# MODUL_BRIDGE_V100.net
KiCad netlist of a schematic drawn in EAGLE
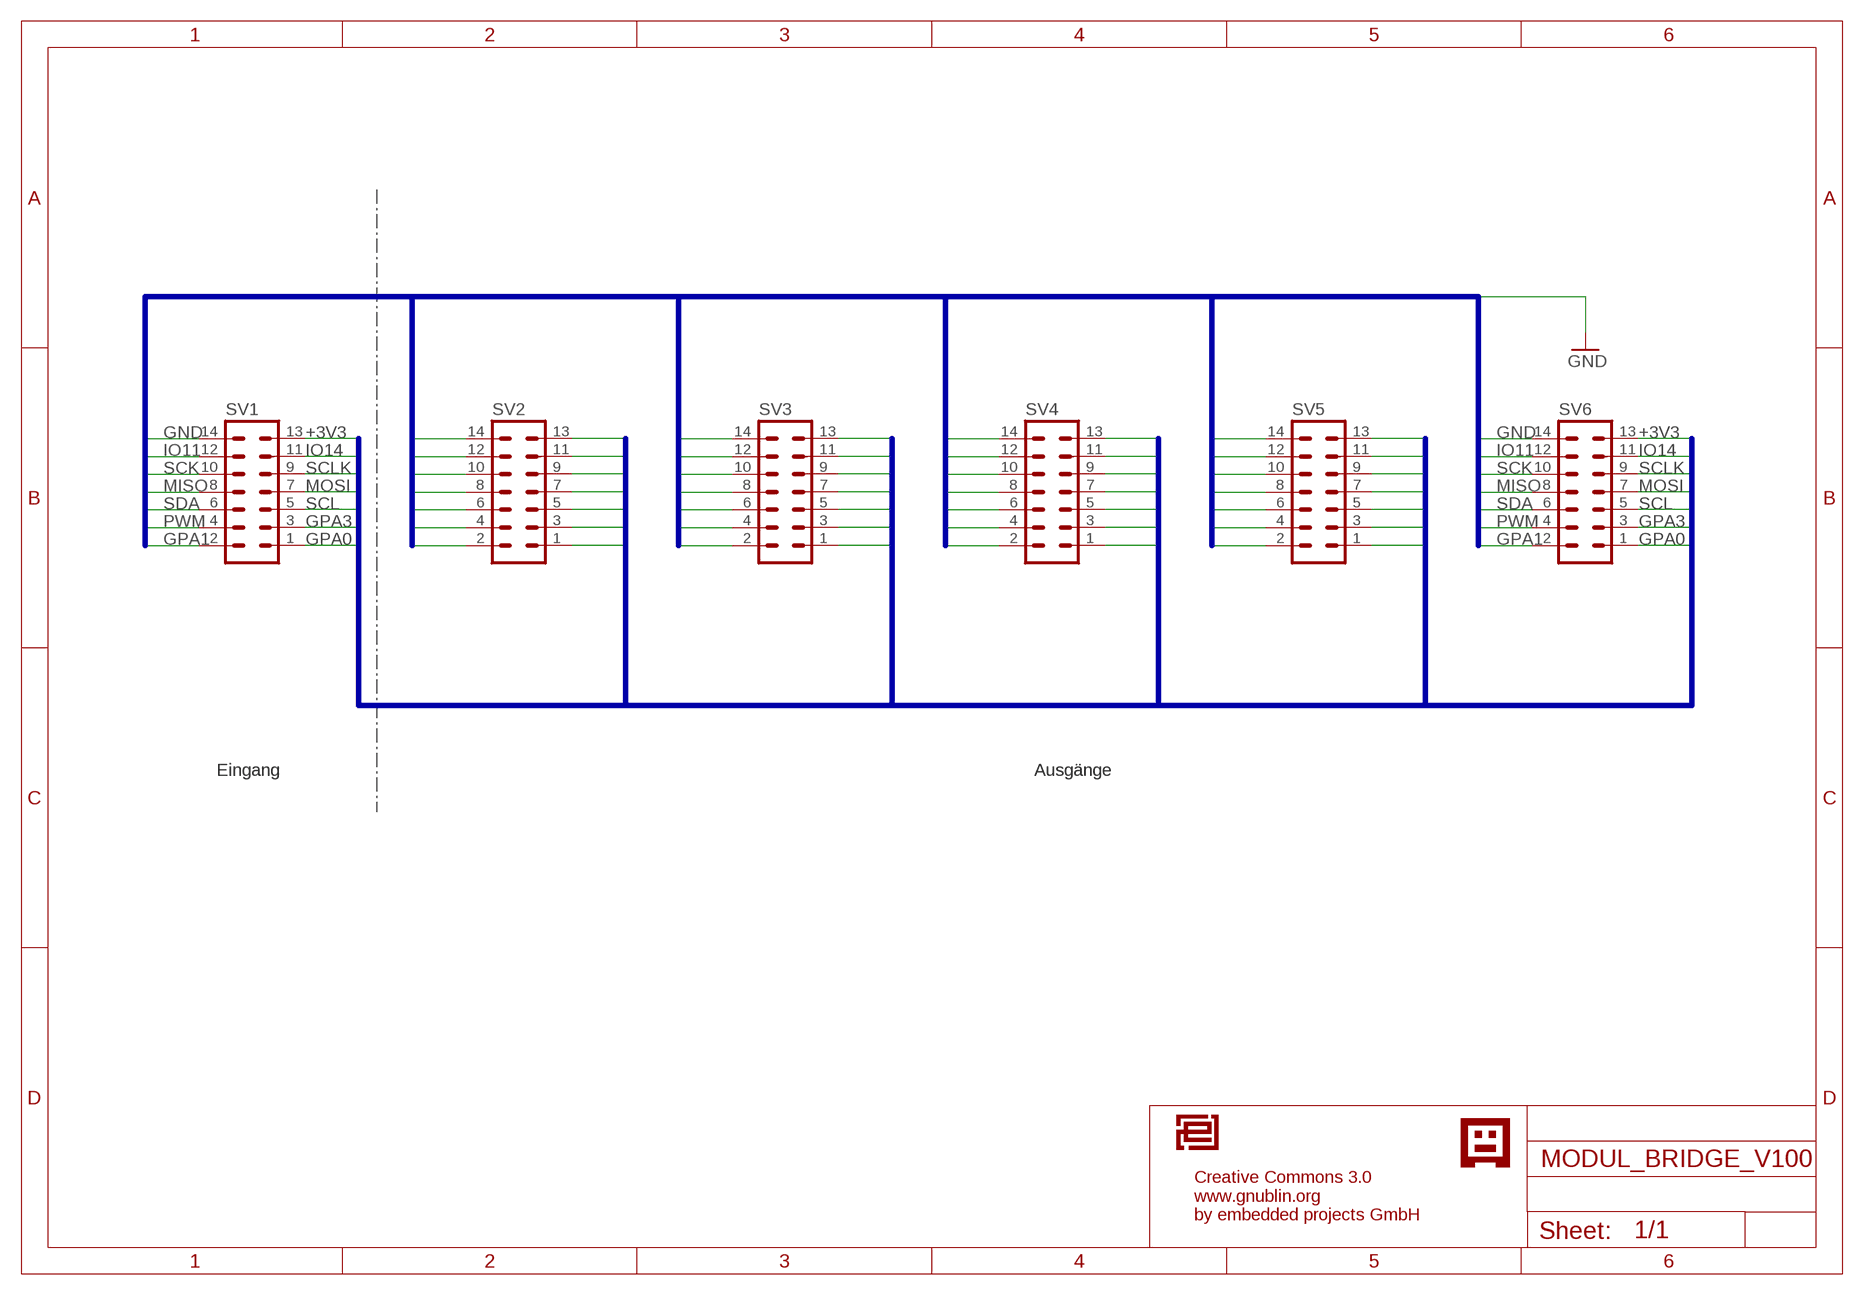
[diagram p0: schematic, sheet 1]

(export (version "E")
  (design (tool "Eeschema 10.0.6"))
  (components
    (comp (ref "SV1")
      (value "ML14")
      (footprint "eagle-import:ML14")
      (libsource (lib "eagle-import") (part "ML14"))
    )
    (comp (ref "SV2")
      (value "ML14")
      (footprint "eagle-import:ML14")
      (libsource (lib "eagle-import") (part "ML14"))
    )
    (comp (ref "SV3")
      (value "ML14")
      (footprint "eagle-import:ML14")
      (libsource (lib "eagle-import") (part "ML14"))
    )
    (comp (ref "SV4")
      (value "ML14")
      (footprint "eagle-import:ML14")
      (libsource (lib "eagle-import") (part "ML14"))
    )
    (comp (ref "SV5")
      (value "ML14")
      (footprint "eagle-import:ML14")
      (libsource (lib "eagle-import") (part "ML14"))
    )
    (comp (ref "SV6")
      (value "ML14")
      (footprint "eagle-import:ML14")
      (libsource (lib "eagle-import") (part "ML14"))
    )
    (comp (ref "U$1")
      (value "EPLOGOSIEB")
      (footprint "eagle-import:EPLOGOSIEBDRUCK")
      (libsource (lib "eagle-import") (part "EPLOGOSIEB"))
    )
    (comp (ref "U$2")
      (value "GNUBLINLOGOSIEB")
      (footprint "eagle-import:GNUSIEBDRUCK")
      (libsource (lib "eagle-import") (part "GNUBLINLOGOSIEB"))
    )
  )
  (nets
    (net (code "1") (name "/+3V3") (class "Default")
      (node (ref "SV1") (pin "13") (pinfunction "13_13") (pintype "passive"))
      (node (ref "SV2") (pin "13") (pinfunction "13_13") (pintype "passive"))
      (node (ref "SV3") (pin "13") (pinfunction "13_13") (pintype "passive"))
      (node (ref "SV4") (pin "13") (pinfunction "13_13") (pintype "passive"))
      (node (ref "SV5") (pin "13") (pinfunction "13_13") (pintype "passive"))
      (node (ref "SV6") (pin "13") (pinfunction "13_13") (pintype "passive"))
    )
    (net (code "2") (name "/GPA0") (class "Default")
      (node (ref "SV1") (pin "1") (pinfunction "1_1") (pintype "passive"))
      (node (ref "SV2") (pin "1") (pinfunction "1_1") (pintype "passive"))
      (node (ref "SV3") (pin "1") (pinfunction "1_1") (pintype "passive"))
      (node (ref "SV4") (pin "1") (pinfunction "1_1") (pintype "passive"))
      (node (ref "SV5") (pin "1") (pinfunction "1_1") (pintype "passive"))
      (node (ref "SV6") (pin "1") (pinfunction "1_1") (pintype "passive"))
    )
    (net (code "3") (name "/GPA1") (class "Default")
      (node (ref "SV1") (pin "2") (pinfunction "2_2") (pintype "passive"))
      (node (ref "SV2") (pin "2") (pinfunction "2_2") (pintype "passive"))
      (node (ref "SV3") (pin "2") (pinfunction "2_2") (pintype "passive"))
      (node (ref "SV4") (pin "2") (pinfunction "2_2") (pintype "passive"))
      (node (ref "SV5") (pin "2") (pinfunction "2_2") (pintype "passive"))
      (node (ref "SV6") (pin "2") (pinfunction "2_2") (pintype "passive"))
    )
    (net (code "4") (name "/GPA3") (class "Default")
      (node (ref "SV1") (pin "3") (pinfunction "3_3") (pintype "passive"))
      (node (ref "SV2") (pin "3") (pinfunction "3_3") (pintype "passive"))
      (node (ref "SV3") (pin "3") (pinfunction "3_3") (pintype "passive"))
      (node (ref "SV4") (pin "3") (pinfunction "3_3") (pintype "passive"))
      (node (ref "SV5") (pin "3") (pinfunction "3_3") (pintype "passive"))
      (node (ref "SV6") (pin "3") (pinfunction "3_3") (pintype "passive"))
    )
    (net (code "5") (name "/IO11") (class "Default")
      (node (ref "SV1") (pin "12") (pinfunction "12_12") (pintype "passive"))
      (node (ref "SV2") (pin "12") (pinfunction "12_12") (pintype "passive"))
      (node (ref "SV3") (pin "12") (pinfunction "12_12") (pintype "passive"))
      (node (ref "SV4") (pin "12") (pinfunction "12_12") (pintype "passive"))
      (node (ref "SV5") (pin "12") (pinfunction "12_12") (pintype "passive"))
      (node (ref "SV6") (pin "12") (pinfunction "12_12") (pintype "passive"))
    )
    (net (code "6") (name "/IO14") (class "Default")
      (node (ref "SV1") (pin "11") (pinfunction "11_11") (pintype "passive"))
      (node (ref "SV2") (pin "11") (pinfunction "11_11") (pintype "passive"))
      (node (ref "SV3") (pin "11") (pinfunction "11_11") (pintype "passive"))
      (node (ref "SV4") (pin "11") (pinfunction "11_11") (pintype "passive"))
      (node (ref "SV5") (pin "11") (pinfunction "11_11") (pintype "passive"))
      (node (ref "SV6") (pin "11") (pinfunction "11_11") (pintype "passive"))
    )
    (net (code "7") (name "/MISO") (class "Default")
      (node (ref "SV1") (pin "8") (pinfunction "8_8") (pintype "passive"))
      (node (ref "SV2") (pin "8") (pinfunction "8_8") (pintype "passive"))
      (node (ref "SV3") (pin "8") (pinfunction "8_8") (pintype "passive"))
      (node (ref "SV4") (pin "8") (pinfunction "8_8") (pintype "passive"))
      (node (ref "SV5") (pin "8") (pinfunction "8_8") (pintype "passive"))
      (node (ref "SV6") (pin "8") (pinfunction "8_8") (pintype "passive"))
    )
    (net (code "8") (name "/MOSI") (class "Default")
      (node (ref "SV1") (pin "7") (pinfunction "7_7") (pintype "passive"))
      (node (ref "SV2") (pin "7") (pinfunction "7_7") (pintype "passive"))
      (node (ref "SV3") (pin "7") (pinfunction "7_7") (pintype "passive"))
      (node (ref "SV4") (pin "7") (pinfunction "7_7") (pintype "passive"))
      (node (ref "SV5") (pin "7") (pinfunction "7_7") (pintype "passive"))
      (node (ref "SV6") (pin "7") (pinfunction "7_7") (pintype "passive"))
    )
    (net (code "9") (name "/PWM") (class "Default")
      (node (ref "SV1") (pin "4") (pinfunction "4_4") (pintype "passive"))
      (node (ref "SV2") (pin "4") (pinfunction "4_4") (pintype "passive"))
      (node (ref "SV3") (pin "4") (pinfunction "4_4") (pintype "passive"))
      (node (ref "SV4") (pin "4") (pinfunction "4_4") (pintype "passive"))
      (node (ref "SV5") (pin "4") (pinfunction "4_4") (pintype "passive"))
      (node (ref "SV6") (pin "4") (pinfunction "4_4") (pintype "passive"))
    )
    (net (code "10") (name "/SCK") (class "Default")
      (node (ref "SV1") (pin "10") (pinfunction "10_10") (pintype "passive"))
      (node (ref "SV2") (pin "10") (pinfunction "10_10") (pintype "passive"))
      (node (ref "SV3") (pin "10") (pinfunction "10_10") (pintype "passive"))
      (node (ref "SV4") (pin "10") (pinfunction "10_10") (pintype "passive"))
      (node (ref "SV5") (pin "10") (pinfunction "10_10") (pintype "passive"))
      (node (ref "SV6") (pin "10") (pinfunction "10_10") (pintype "passive"))
    )
    (net (code "11") (name "/SCL") (class "Default")
      (node (ref "SV1") (pin "5") (pinfunction "5_5") (pintype "passive"))
      (node (ref "SV2") (pin "5") (pinfunction "5_5") (pintype "passive"))
      (node (ref "SV3") (pin "5") (pinfunction "5_5") (pintype "passive"))
      (node (ref "SV4") (pin "5") (pinfunction "5_5") (pintype "passive"))
      (node (ref "SV5") (pin "5") (pinfunction "5_5") (pintype "passive"))
      (node (ref "SV6") (pin "5") (pinfunction "5_5") (pintype "passive"))
    )
    (net (code "12") (name "/SCLK") (class "Default")
      (node (ref "SV1") (pin "9") (pinfunction "9_9") (pintype "passive"))
      (node (ref "SV2") (pin "9") (pinfunction "9_9") (pintype "passive"))
      (node (ref "SV3") (pin "9") (pinfunction "9_9") (pintype "passive"))
      (node (ref "SV4") (pin "9") (pinfunction "9_9") (pintype "passive"))
      (node (ref "SV5") (pin "9") (pinfunction "9_9") (pintype "passive"))
      (node (ref "SV6") (pin "9") (pinfunction "9_9") (pintype "passive"))
    )
    (net (code "13") (name "/SDA") (class "Default")
      (node (ref "SV1") (pin "6") (pinfunction "6_6") (pintype "passive"))
      (node (ref "SV2") (pin "6") (pinfunction "6_6") (pintype "passive"))
      (node (ref "SV3") (pin "6") (pinfunction "6_6") (pintype "passive"))
      (node (ref "SV4") (pin "6") (pinfunction "6_6") (pintype "passive"))
      (node (ref "SV5") (pin "6") (pinfunction "6_6") (pintype "passive"))
      (node (ref "SV6") (pin "6") (pinfunction "6_6") (pintype "passive"))
    )
    (net (code "14") (name "GND") (class "Default")
      (node (ref "SV1") (pin "14") (pinfunction "14_14") (pintype "passive"))
      (node (ref "SV2") (pin "14") (pinfunction "14_14") (pintype "passive"))
      (node (ref "SV3") (pin "14") (pinfunction "14_14") (pintype "passive"))
      (node (ref "SV4") (pin "14") (pinfunction "14_14") (pintype "passive"))
      (node (ref "SV5") (pin "14") (pinfunction "14_14") (pintype "passive"))
      (node (ref "SV6") (pin "14") (pinfunction "14_14") (pintype "passive"))
    )
  )
)
